# MostekH.net
KiCad netlist of a schematic drawn in Altium Designer
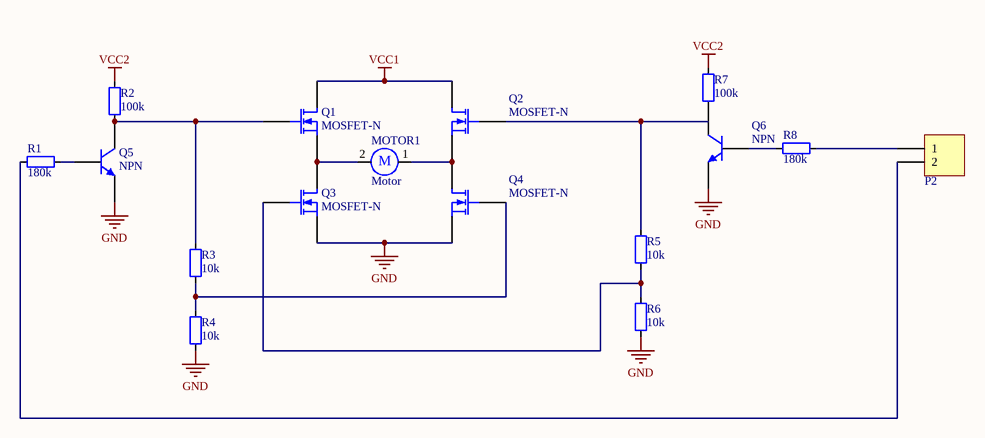
[diagram p0: MostekH.SchDoc]

(export (version "E")
  (design (tool "Eeschema 10.0.6"))
  (components
    (comp (ref "MOTOR1")
      (value "Motor")
      (footprint "HDR1X2")
      (description "Motor, General Kind")
      (fields (field (name "PUBLISHER") "Altium Limited"))
      (libsource (lib "KNR_Kurs") (part "Motor"))
    )
    (comp (ref "P2")
      (value "HDR1X2")
      (footprint "HDR1X2")
      (description "Header, 2-Pin")
      (fields (field (name "PUBLISHER") "Altium Limited"))
      (libsource (lib "KNR_Kurs") (part "HDR1X2"))
    )
    (comp (ref "Q1")
      (value "MOSFET-N")
      (footprint "E3")
      (description "N-Channel MOSFET")
      (fields (field (name "PUBLISHER") "Altium Limited"))
      (libsource (lib "Miscellaneous Devices") (part "MOSFET-N"))
    )
    (comp (ref "Q2")
      (value "MOSFET-N")
      (footprint "E3")
      (description "N-Channel MOSFET")
      (fields (field (name "PUBLISHER") "Altium Limited"))
      (libsource (lib "Miscellaneous Devices") (part "MOSFET-N"))
    )
    (comp (ref "Q3")
      (value "MOSFET-N")
      (footprint "E3")
      (description "N-Channel MOSFET")
      (fields (field (name "PUBLISHER") "Altium Limited"))
      (libsource (lib "Miscellaneous Devices") (part "MOSFET-N"))
    )
    (comp (ref "Q4")
      (value "MOSFET-N")
      (footprint "E3")
      (description "N-Channel MOSFET")
      (fields (field (name "PUBLISHER") "Altium Limited"))
      (libsource (lib "Miscellaneous Devices") (part "MOSFET-N"))
    )
    (comp (ref "Q5")
      (value "NPN")
      (footprint "TO-226-AA")
      (description "NPN Bipolar Transistor")
      (fields (field (name "PUBLISHER") "Altium Limited"))
      (libsource (lib "Miscellaneous Devices") (part "NPN"))
    )
    (comp (ref "Q6")
      (value "NPN")
      (footprint "TO-226-AA")
      (description "NPN Bipolar Transistor")
      (fields (field (name "PUBLISHER") "Altium Limited"))
      (libsource (lib "Miscellaneous Devices") (part "NPN"))
    )
    (comp (ref "R1")
      (value "180k")
      (footprint "RESC0402")
      (description "Resistior")
      (libsource (lib "KNR_Kurs") (part "RES"))
    )
    (comp (ref "R2")
      (value "100k")
      (footprint "RESC0402")
      (description "Resistior")
      (libsource (lib "") (part "RES_1"))
    )
    (comp (ref "R3")
      (value "10k")
      (footprint "RESC0402")
      (description "Resistior")
      (libsource (lib "") (part "RES_1"))
    )
    (comp (ref "R4")
      (value "10k")
      (footprint "RESC0402")
      (description "Resistior")
      (libsource (lib "") (part "RES_1"))
    )
    (comp (ref "R5")
      (value "10k")
      (footprint "RESC0402")
      (description "Resistior")
      (libsource (lib "") (part "RES_1"))
    )
    (comp (ref "R6")
      (value "10k")
      (footprint "RESC0402")
      (description "Resistior")
      (libsource (lib "") (part "RES_1"))
    )
    (comp (ref "R7")
      (value "100k")
      (footprint "RESC0402")
      (description "Resistior")
      (libsource (lib "") (part "RES_1"))
    )
    (comp (ref "R8")
      (value "180k")
      (footprint "RESC0402")
      (description "Resistior")
      (libsource (lib "KNR_Kurs") (part "RES"))
    )
  )
  (nets
    (net (code "1") (name "GND") (class "Default")
      (node (ref "Q3") (pin "3") (pinfunction "S_3") (pintype "passive"))
      (node (ref "Q4") (pin "3") (pinfunction "S_3") (pintype "passive"))
      (node (ref "Q5") (pin "3") (pinfunction "E_3") (pintype "passive"))
      (node (ref "Q6") (pin "3") (pinfunction "E_3") (pintype "passive"))
      (node (ref "R4") (pin "1") (pinfunction "1_1") (pintype "passive"))
      (node (ref "R6") (pin "1") (pinfunction "1_1") (pintype "passive"))
    )
    (net (code "2") (name "Net-(P2-Pad1)") (class "Default")
      (node (ref "P2") (pin "1") (pinfunction "1_1") (pintype "passive"))
      (node (ref "R8") (pin "1") (pinfunction "1_1") (pintype "passive"))
    )
    (net (code "3") (name "Net-(P2-Pad2)") (class "Default")
      (node (ref "P2") (pin "2") (pinfunction "2_2") (pintype "passive"))
      (node (ref "R1") (pin "2") (pinfunction "2_2") (pintype "passive"))
    )
    (net (code "4") (name "Net-(Q1-G)") (class "Default")
      (node (ref "Q1") (pin "2") (pinfunction "G_2") (pintype "passive"))
      (node (ref "Q5") (pin "1") (pinfunction "C_1") (pintype "passive"))
      (node (ref "R2") (pin "1") (pinfunction "1_1") (pintype "passive"))
      (node (ref "R3") (pin "2") (pinfunction "2_2") (pintype "passive"))
    )
    (net (code "5") (name "Net-(Q1-S)") (class "Default")
      (node (ref "MOTOR1") (pin "2") (pinfunction "2_2") (pintype "passive"))
      (node (ref "Q1") (pin "3") (pinfunction "S_3") (pintype "passive"))
      (node (ref "Q3") (pin "1") (pinfunction "D_1") (pintype "passive"))
    )
    (net (code "6") (name "Net-(Q2-G)") (class "Default")
      (node (ref "Q2") (pin "2") (pinfunction "G_2") (pintype "passive"))
      (node (ref "R5") (pin "2") (pinfunction "2_2") (pintype "passive"))
    )
    (net (code "7") (name "Net-(Q2-S)") (class "Default")
      (node (ref "MOTOR1") (pin "1") (pinfunction "1_1") (pintype "passive"))
      (node (ref "Q2") (pin "3") (pinfunction "S_3") (pintype "passive"))
      (node (ref "Q4") (pin "1") (pinfunction "D_1") (pintype "passive"))
    )
    (net (code "8") (name "Net-(Q3-G)") (class "Default")
      (node (ref "Q3") (pin "2") (pinfunction "G_2") (pintype "passive"))
      (node (ref "R5") (pin "1") (pinfunction "1_1") (pintype "passive"))
      (node (ref "R6") (pin "2") (pinfunction "2_2") (pintype "passive"))
    )
    (net (code "9") (name "Net-(Q4-G)") (class "Default")
      (node (ref "Q4") (pin "2") (pinfunction "G_2") (pintype "passive"))
      (node (ref "R3") (pin "1") (pinfunction "1_1") (pintype "passive"))
      (node (ref "R4") (pin "2") (pinfunction "2_2") (pintype "passive"))
    )
    (net (code "10") (name "Net-(Q5-B)") (class "Default")
      (node (ref "Q5") (pin "2") (pinfunction "B_2") (pintype "passive"))
      (node (ref "R1") (pin "1") (pinfunction "1_1") (pintype "passive"))
    )
    (net (code "11") (name "Net-(Q6-B)") (class "Default")
      (node (ref "Q6") (pin "2") (pinfunction "B_2") (pintype "passive"))
      (node (ref "R8") (pin "2") (pinfunction "2_2") (pintype "passive"))
    )
    (net (code "12") (name "Net-(Q6-C)") (class "Default")
      (node (ref "Q6") (pin "1") (pinfunction "C_1") (pintype "passive"))
      (node (ref "R7") (pin "1") (pinfunction "1_1") (pintype "passive"))
    )
    (net (code "13") (name "VCC1") (class "Default")
      (node (ref "Q1") (pin "1") (pinfunction "D_1") (pintype "passive"))
      (node (ref "Q2") (pin "1") (pinfunction "D_1") (pintype "passive"))
    )
    (net (code "14") (name "VCC2") (class "Default")
      (node (ref "R2") (pin "2") (pinfunction "2_2") (pintype "passive"))
      (node (ref "R7") (pin "2") (pinfunction "2_2") (pintype "passive"))
    )
  )
)
